# lcd.net
KiCad netlist of a schematic drawn in Altium Designer
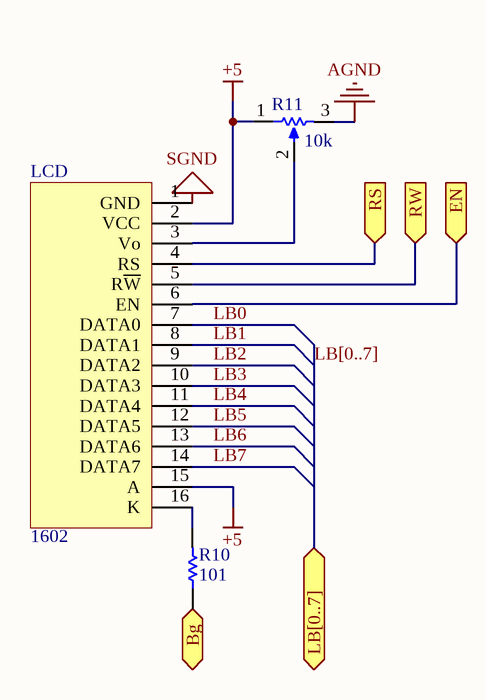
[diagram p0: lcd.SchDoc]

(export (version "E")
  (design (tool "Eeschema 10.0.6"))
  (components
    (comp (ref "LCD")
      (value "1602")
      (footprint "1602(DIP)")
      (description "lcd1602")
      (libsource (lib "Self Establish") (part "1602"))
    )
    (comp (ref "R10")
      (value "101")
      (footprint "0805(M)")
      (fields (field (name "Comment") "Res"))
      (libsource (lib "Self Establish") (part "Res"))
    )
    (comp (ref "R11")
      (value "10k")
      (footprint "3296W(DIP)")
      (description "电位计")
      (fields (field (name "Comment") "Rpot"))
      (libsource (lib "Self Establish") (part "Rpot"))
    )
  )
  (nets
    (net (code "1") (name "+5") (class "Default")
      (node (ref "LCD") (pin "15") (pinfunction "A_15") (pintype "passive"))
      (node (ref "LCD") (pin "2") (pinfunction "VCC_2") (pintype "passive"))
      (node (ref "R11") (pin "1") (pinfunction "TOP_1") (pintype "passive"))
    )
    (net (code "2") (name "/Bg") (class "Default")
      (node (ref "R10") (pin "1") (pinfunction "1_1") (pintype "passive"))
    )
    (net (code "3") (name "/EN") (class "Default")
      (node (ref "LCD") (pin "6") (pinfunction "EN_6") (pintype "passive"))
    )
    (net (code "4") (name "/LB0") (class "Default")
      (node (ref "LCD") (pin "7") (pinfunction "DATA0_7") (pintype "passive"))
    )
    (net (code "5") (name "/LB1") (class "Default")
      (node (ref "LCD") (pin "8") (pinfunction "DATA1_8") (pintype "passive"))
    )
    (net (code "6") (name "/LB2") (class "Default")
      (node (ref "LCD") (pin "9") (pinfunction "DATA2_9") (pintype "passive"))
    )
    (net (code "7") (name "/LB3") (class "Default")
      (node (ref "LCD") (pin "10") (pinfunction "DATA3_10") (pintype "passive"))
    )
    (net (code "8") (name "/LB4") (class "Default")
      (node (ref "LCD") (pin "11") (pinfunction "DATA4_11") (pintype "passive"))
    )
    (net (code "9") (name "/LB5") (class "Default")
      (node (ref "LCD") (pin "12") (pinfunction "DATA5_12") (pintype "passive"))
    )
    (net (code "10") (name "/LB6") (class "Default")
      (node (ref "LCD") (pin "13") (pinfunction "DATA6_13") (pintype "passive"))
    )
    (net (code "11") (name "/LB7") (class "Default")
      (node (ref "LCD") (pin "14") (pinfunction "DATA7_14") (pintype "passive"))
    )
    (net (code "13") (name "/RS") (class "Default")
      (node (ref "LCD") (pin "4") (pinfunction "RS_4") (pintype "passive"))
    )
    (net (code "14") (name "/RW") (class "Default")
      (node (ref "LCD") (pin "5") (pinfunction "R~{W}_5") (pintype "passive"))
    )
    (net (code "15") (name "AGND") (class "Default")
      (node (ref "R11") (pin "3") (pinfunction "BOT_3") (pintype "passive"))
    )
    (net (code "16") (name "Net-(LCD-K)") (class "Default")
      (node (ref "LCD") (pin "16") (pinfunction "K_16") (pintype "passive"))
      (node (ref "R10") (pin "2") (pinfunction "2_2") (pintype "passive"))
    )
    (net (code "17") (name "Net-(LCD-Vo)") (class "Default")
      (node (ref "LCD") (pin "3") (pinfunction "Vo_3") (pintype "passive"))
      (node (ref "R11") (pin "2") (pinfunction "TAP_2") (pintype "passive"))
    )
    (net (code "18") (name "SGND") (class "Default")
      (node (ref "LCD") (pin "1") (pinfunction "GND_1") (pintype "passive"))
    )
  )
)
